# CAN.net
KiCad netlist of a schematic drawn in Altium Designer
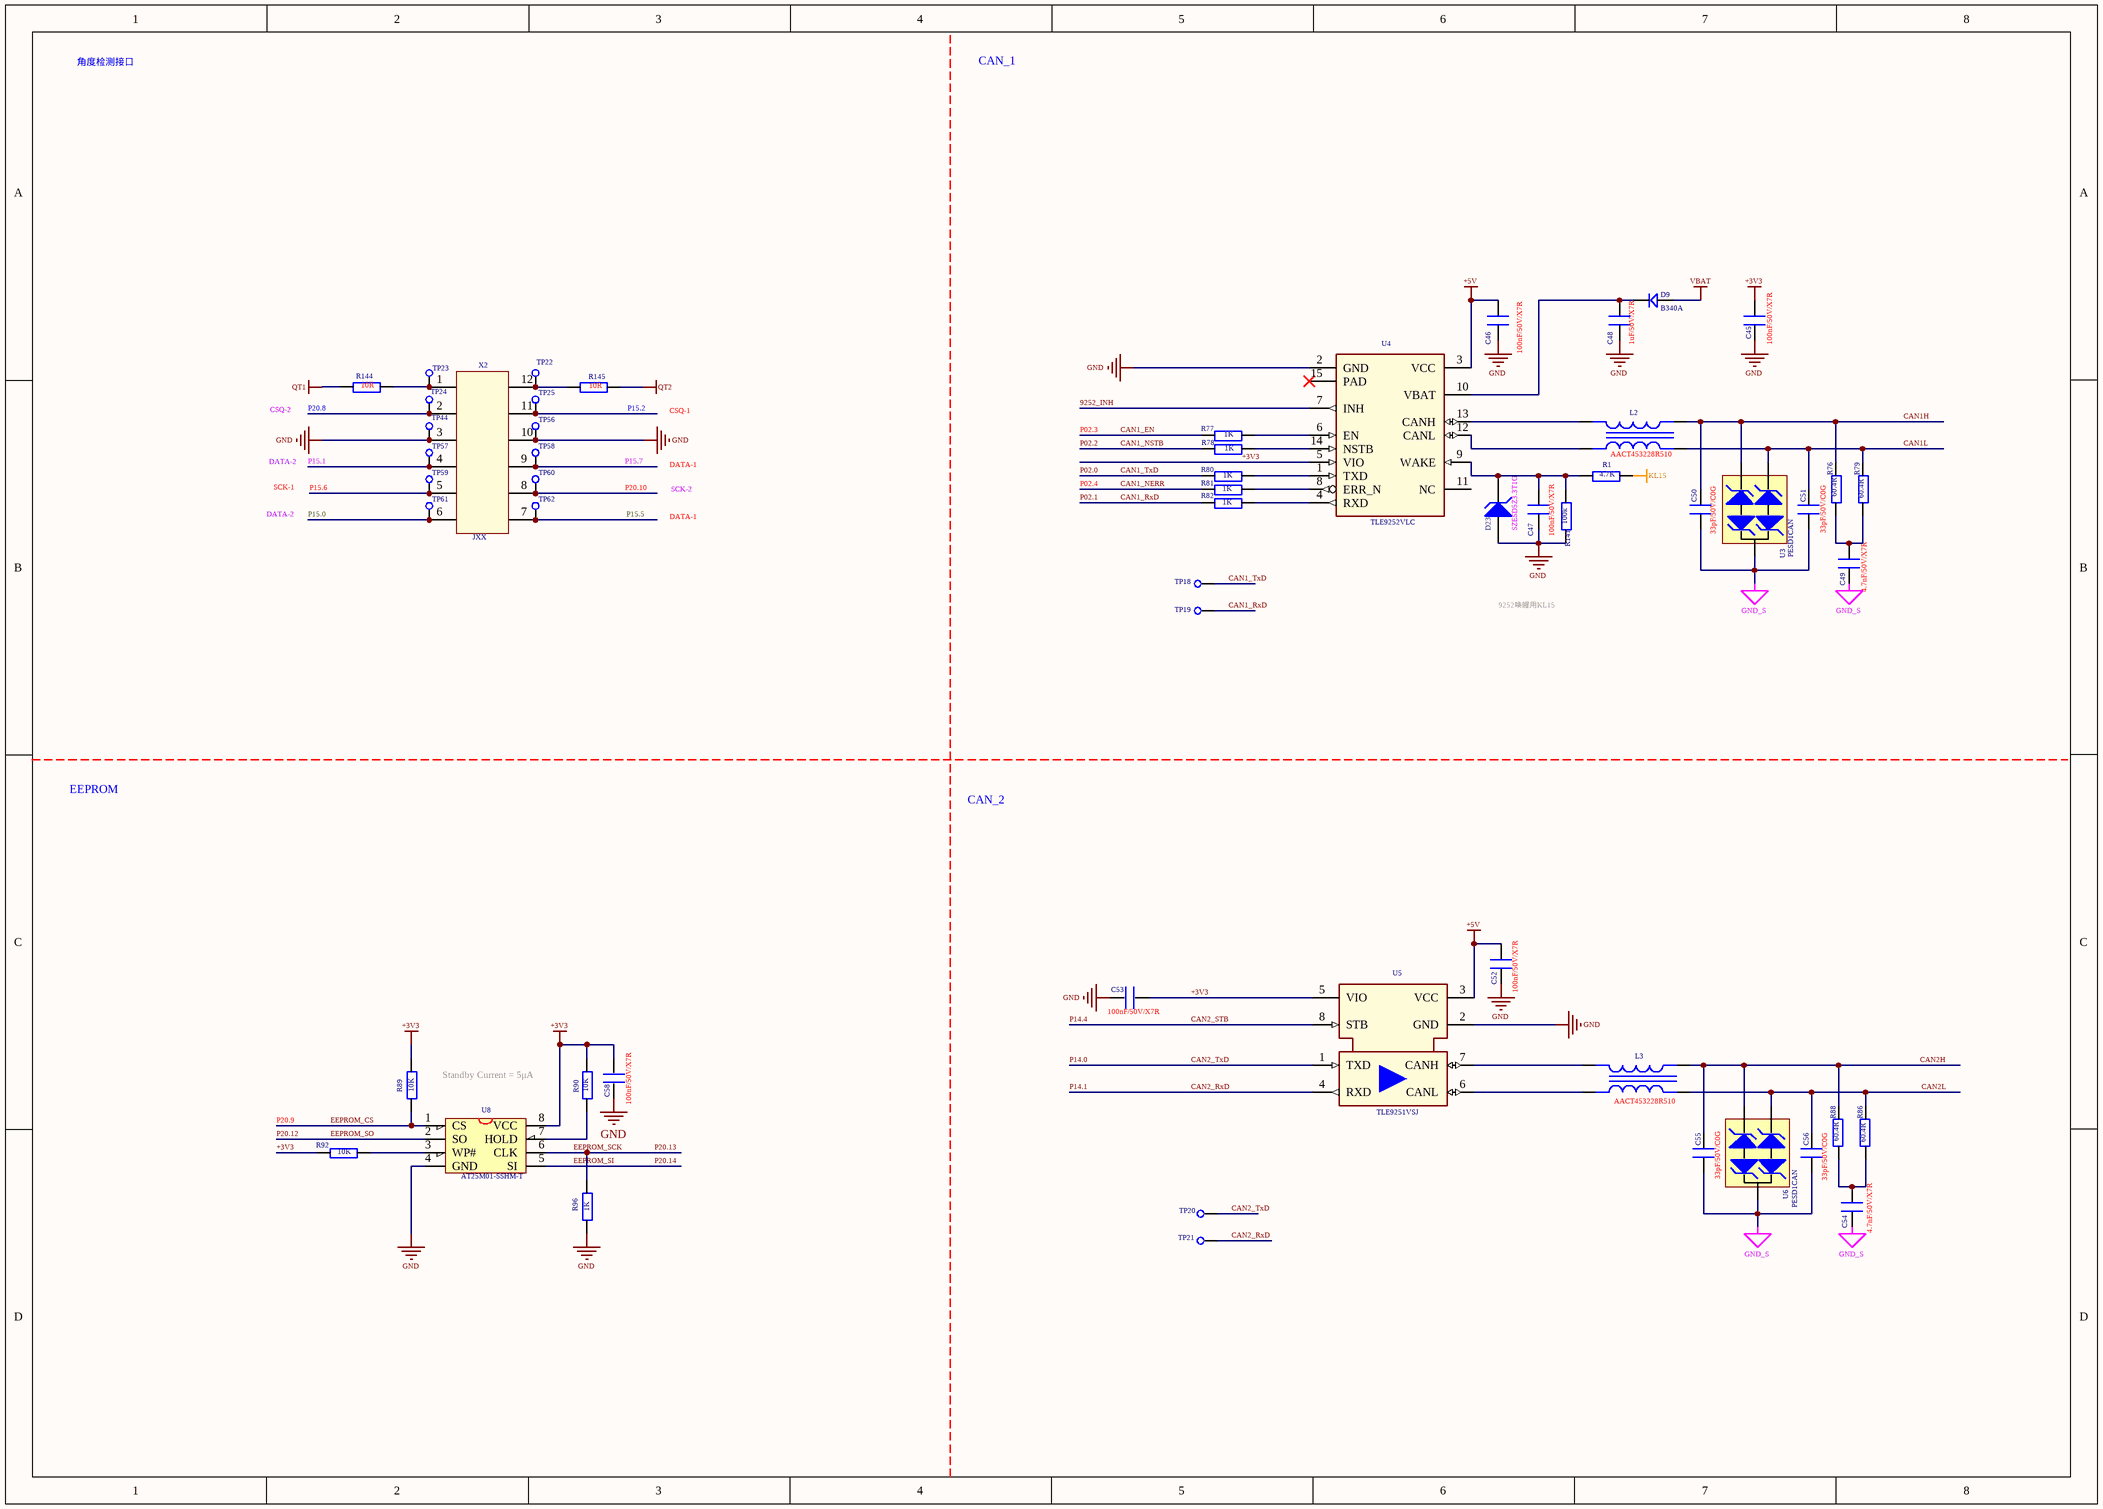
[diagram p0: CAN.SchDoc]

(export (version "E")
  (design (tool "Eeschema 10.0.6"))
  (components
    (comp (ref "C45")
      (value "100nF/50V/X7R")
      (footprint "C0603P")
      (libsource (lib "WarShip V3 STM32103封装库") (part "C"))
    )
    (comp (ref "C46")
      (value "100nF/50V/X7R")
      (footprint "C0603P")
      (libsource (lib "WarShip V3 STM32103封装库") (part "C"))
    )
    (comp (ref "C47")
      (value "100nF/50V/X7R")
      (footprint "C0603P")
      (libsource (lib "WarShip V3 STM32103封装库") (part "C"))
    )
    (comp (ref "C48")
      (value "1uF/50V/X7R")
      (footprint "C0805")
      (libsource (lib "WarShip V3 STM32103封装库") (part "C"))
    )
    (comp (ref "C49")
      (value "4.7nF/50V/X7R")
      (footprint "C0603P")
      (libsource (lib "WarShip V3 STM32103封装库") (part "C"))
    )
    (comp (ref "C50")
      (value "33pF/50V/C0G")
      (footprint "C0603P")
      (libsource (lib "WarShip V3 STM32103封装库") (part "C"))
    )
    (comp (ref "C51")
      (value "33pF/50V/C0G")
      (footprint "C0603P")
      (libsource (lib "WarShip V3 STM32103封装库") (part "C"))
    )
    (comp (ref "C52")
      (value "100nF/50V/X7R")
      (footprint "C0603P")
      (libsource (lib "WarShip V3 STM32103封装库") (part "C"))
    )
    (comp (ref "C53")
      (value "100nF/50V/X7R")
      (footprint "C0603P")
      (libsource (lib "WarShip V3 STM32103封装库") (part "C"))
    )
    (comp (ref "C54")
      (value "4.7nF/50V/X7R")
      (footprint "C0603P")
      (libsource (lib "WarShip V3 STM32103封装库") (part "C"))
    )
    (comp (ref "C55")
      (value "33pF/50V/C0G")
      (footprint "C0603P")
      (libsource (lib "WarShip V3 STM32103封装库") (part "C"))
    )
    (comp (ref "C56")
      (value "33pF/50V/C0G")
      (footprint "C0603P")
      (libsource (lib "WarShip V3 STM32103封装库") (part "C"))
    )
    (comp (ref "C58")
      (value "100nF/50V/X7R")
      (footprint "C0603P")
      (libsource (lib "WarShip V3 STM32103封装库") (part "C"))
    )
    (comp (ref "D9")
      (value "B340A")
      (footprint "DO-214AC")
      (libsource (lib "WarShip V3 STM32103封装库") (part "D"))
    )
    (comp (ref "D23")
      (value "SZESD5Z3.3T1G")
      (footprint "SOD-523F")
      (description "Zener Diode")
      (fields (field (name "PUBLISHER") "Altium Limited"))
      (libsource (lib "Miscellaneous Devices") (part "D Zener"))
    )
    (comp (ref "L2")
      (value "AACT453228R510")
      (footprint "ACT45B")
      (libsource (lib "zs_lib_wgs") (part "ACT45B-510-2P"))
    )
    (comp (ref "L3")
      (value "AACT453228R510")
      (footprint "ACT45B")
      (libsource (lib "zs_lib_wgs") (part "ACT45B-510-2P"))
    )
    (comp (ref "R1") (value "4.7K") (footprint "0603P") (libsource (lib "WarShip V3 STM32103封装库") (part "R")))
    (comp (ref "R76")
      (value "60.4R")
      (footprint "0603P")
      (libsource (lib "WarShip V3 STM32103封装库") (part "R"))
    )
    (comp (ref "R77") (value "1K") (footprint "0603P") (libsource (lib "WarShip V3 STM32103封装库") (part "R")))
    (comp (ref "R78") (value "1K") (footprint "0603P") (libsource (lib "WarShip V3 STM32103封装库") (part "R")))
    (comp (ref "R79")
      (value "60.4R")
      (footprint "0603P")
      (libsource (lib "WarShip V3 STM32103封装库") (part "R"))
    )
    (comp (ref "R80") (value "1K") (footprint "0603P") (libsource (lib "WarShip V3 STM32103封装库") (part "R")))
    (comp (ref "R81") (value "1K") (footprint "0603P") (libsource (lib "WarShip V3 STM32103封装库") (part "R")))
    (comp (ref "R82") (value "1K") (footprint "0603P") (libsource (lib "WarShip V3 STM32103封装库") (part "R")))
    (comp (ref "R86")
      (value "60.4R")
      (footprint "0603P")
      (libsource (lib "WarShip V3 STM32103封装库") (part "R"))
    )
    (comp (ref "R88")
      (value "60.4R")
      (footprint "0603P")
      (libsource (lib "WarShip V3 STM32103封装库") (part "R"))
    )
    (comp (ref "R89") (value "10K") (footprint "0603P") (libsource (lib "WarShip V3 STM32103封装库") (part "R")))
    (comp (ref "R90") (value "10K") (footprint "0603P") (libsource (lib "WarShip V3 STM32103封装库") (part "R")))
    (comp (ref "R92") (value "10K") (footprint "0603P") (libsource (lib "WarShip V3 STM32103封装库") (part "R")))
    (comp (ref "R96") (value "1K") (footprint "0603P") (libsource (lib "WarShip V3 STM32103封装库") (part "R")))
    (comp (ref "R141")
      (value "100k")
      (footprint "0603P")
      (libsource (lib "WarShip V3 STM32103封装库") (part "R"))
    )
    (comp (ref "R144")
      (value "10R")
      (footprint "0603P")
      (libsource (lib "WarShip V3 STM32103封装库") (part "R"))
    )
    (comp (ref "R145")
      (value "10R")
      (footprint "0603P")
      (libsource (lib "WarShip V3 STM32103封装库") (part "R"))
    )
    (comp (ref "TP18") (value "测试点") (footprint "测试点") (libsource (lib "") (part "测试点_1")))
    (comp (ref "TP19") (value "测试点") (footprint "测试点") (libsource (lib "") (part "测试点_1")))
    (comp (ref "TP20") (value "测试点") (footprint "测试点") (libsource (lib "") (part "测试点_1")))
    (comp (ref "TP21") (value "测试点") (footprint "测试点") (libsource (lib "") (part "测试点_1")))
    (comp (ref "TP22") (value "测试点") (footprint "测试点") (libsource (lib "yds") (part "测试点")))
    (comp (ref "TP23") (value "测试点") (footprint "测试点") (libsource (lib "yds") (part "测试点")))
    (comp (ref "TP24") (value "测试点") (footprint "测试点") (libsource (lib "yds") (part "测试点")))
    (comp (ref "TP25") (value "测试点") (footprint "测试点") (libsource (lib "yds") (part "测试点")))
    (comp (ref "TP44") (value "测试点") (footprint "测试点") (libsource (lib "yds") (part "测试点")))
    (comp (ref "TP56") (value "测试点") (footprint "测试点") (libsource (lib "yds") (part "测试点")))
    (comp (ref "TP57") (value "测试点") (footprint "测试点") (libsource (lib "yds") (part "测试点")))
    (comp (ref "TP58") (value "测试点") (footprint "测试点") (libsource (lib "yds") (part "测试点")))
    (comp (ref "TP59") (value "测试点") (footprint "测试点") (libsource (lib "yds") (part "测试点")))
    (comp (ref "TP60") (value "测试点") (footprint "测试点") (libsource (lib "yds") (part "测试点")))
    (comp (ref "TP61") (value "测试点") (footprint "测试点") (libsource (lib "yds") (part "测试点")))
    (comp (ref "TP62") (value "测试点") (footprint "测试点") (libsource (lib "yds") (part "测试点")))
    (comp (ref "U3")
      (value "PESD1CAN")
      (footprint "SOT-23R")
      (libsource (lib "zs_lib_wgs") (part "PESD1CAN"))
    )
    (comp (ref "U4")
      (value "TLE9252VLC")
      (footprint "SOP14")
      (description "High Speed CAN FD Transceiver")
      (fields (field (name "MANUFACTURER") "Infineon Technologies"))
      (libsource (lib "yds") (part "TLE9252VLC"))
    )
    (comp (ref "U5")
      (value "TLE9251VSJ")
      (footprint "SOIC127P600X175-8N-3")
      (description "High Speed CAN Transceiver")
      (fields (field (name "MANUFACTURER") "Infineon Technologies"))
      (libsource (lib "yds") (part "TLE9251VSJ"))
    )
    (comp (ref "U6")
      (value "PESD1CAN")
      (footprint "SOT-23R")
      (libsource (lib "zs_lib_wgs") (part "PESD1CAN"))
    )
    (comp (ref "U8")
      (value "AT25M01-SSHM-T")
      (footprint "SOIC-8")
      (description "W25X16;SST25VF016;MX25L1605")
      (libsource (lib "WarShip V3 STM32103封装库") (part "W25X16"))
    )
    (comp (ref "X2") (value "JXX") (footprint "HDR2X6") (libsource (lib "myTY_NEW") (part "JXX")))
  )
  (nets
    (net (code "1") (name "+3V3") (class "Default")
      (node (ref "C45") (pin "1") (pintype "passive"))
      (node (ref "C53") (pin "1") (pintype "passive"))
      (node (ref "C58") (pin "1") (pintype "passive"))
      (node (ref "R89") (pin "2") (pintype "passive"))
      (node (ref "R90") (pin "2") (pintype "passive"))
      (node (ref "R92") (pin "1") (pintype "passive"))
      (node (ref "U4") (pin "5") (pinfunction "VIO_5") (pintype "input"))
      (node (ref "U5") (pin "5") (pinfunction "VIO_5") (pintype "power_in"))
      (node (ref "U8") (pin "8") (pinfunction "VCC_8") (pintype "passive"))
    )
    (net (code "2") (name "+5V") (class "Default")
      (node (ref "C46") (pin "1") (pintype "passive"))
      (node (ref "C52") (pin "2") (pintype "passive"))
      (node (ref "U4") (pin "3") (pinfunction "VCC_3") (pintype "power_in"))
      (node (ref "U5") (pin "3") (pinfunction "VCC_3") (pintype "power_in"))
    )
    (net (code "3") (name "/9252_INH") (class "Default")
      (node (ref "U4") (pin "7") (pinfunction "INH_7") (pintype "output"))
    )
    (net (code "4") (name "/CAN1H") (class "Default")
      (node (ref "C50") (pin "2") (pintype "passive"))
      (node (ref "L2") (pin "3") (pinfunction "Sec-_3") (pintype "passive"))
      (node (ref "R76") (pin "2") (pintype "passive"))
      (node (ref "U3") (pin "2") (pinfunction "2_2") (pintype "passive"))
    )
    (net (code "5") (name "/CAN1L") (class "Default")
      (node (ref "C51") (pin "2") (pintype "passive"))
      (node (ref "L2") (pin "4") (pinfunction "Pri-_4") (pintype "passive"))
      (node (ref "R79") (pin "2") (pintype "passive"))
      (node (ref "U3") (pin "1") (pinfunction "1_1") (pintype "passive"))
    )
    (net (code "6") (name "/CAN1_EN") (class "Default") (node (ref "R77") (pin "1") (pintype "passive")))
    (net (code "7") (name "/CAN1_NERR") (class "Default") (node (ref "R81") (pin "1") (pintype "passive")))
    (net (code "8") (name "/CAN1_NSTB") (class "Default") (node (ref "R78") (pin "1") (pintype "passive")))
    (net (code "9") (name "/CAN1_RxD") (class "Default")
      (node (ref "R82") (pin "1") (pintype "passive"))
      (node (ref "TP19") (pin "1") (pinfunction "1_1") (pintype "passive"))
    )
    (net (code "10") (name "/CAN1_TxD") (class "Default")
      (node (ref "R80") (pin "1") (pintype "passive"))
      (node (ref "TP18") (pin "1") (pinfunction "1_1") (pintype "passive"))
    )
    (net (code "11") (name "/CAN2H") (class "Default")
      (node (ref "C55") (pin "2") (pintype "passive"))
      (node (ref "L3") (pin "3") (pinfunction "Sec-_3") (pintype "passive"))
      (node (ref "R88") (pin "1") (pintype "passive"))
      (node (ref "U6") (pin "2") (pinfunction "2_2") (pintype "passive"))
    )
    (net (code "12") (name "/CAN2L") (class "Default")
      (node (ref "C56") (pin "2") (pintype "passive"))
      (node (ref "L3") (pin "4") (pinfunction "Pri-_4") (pintype "passive"))
      (node (ref "R86") (pin "1") (pintype "passive"))
      (node (ref "U6") (pin "1") (pinfunction "1_1") (pintype "passive"))
    )
    (net (code "13") (name "/CAN2_RxD") (class "Default")
      (node (ref "TP21") (pin "1") (pinfunction "1_1") (pintype "passive"))
      (node (ref "U5") (pin "4") (pinfunction "RXD_4") (pintype "output"))
    )
    (net (code "14") (name "/CAN2_STB") (class "Default")
      (node (ref "U5") (pin "8") (pinfunction "STB_8") (pintype "input"))
    )
    (net (code "15") (name "/CAN2_TxD") (class "Default")
      (node (ref "TP20") (pin "1") (pinfunction "1_1") (pintype "passive"))
      (node (ref "U5") (pin "1") (pinfunction "TXD_1") (pintype "input"))
    )
    (net (code "20") (name "/EEPROM_CS") (class "Default")
      (node (ref "R89") (pin "1") (pintype "passive"))
      (node (ref "U8") (pin "1") (pinfunction "CS_1") (pintype "passive"))
    )
    (net (code "21") (name "/EEPROM_SCK") (class "Default")
      (node (ref "R96") (pin "2") (pintype "passive"))
      (node (ref "U8") (pin "6") (pinfunction "CLK_6") (pintype "passive"))
    )
    (net (code "22") (name "/EEPROM_SI") (class "Default")
      (node (ref "U8") (pin "5") (pinfunction "SI_5") (pintype "passive"))
    )
    (net (code "23") (name "/EEPROM_SO") (class "Default")
      (node (ref "U8") (pin "2") (pinfunction "SO_2") (pintype "passive"))
    )
    (net (code "24") (name "/P15.0") (class "Default")
      (node (ref "TP61") (pin "1") (pinfunction "1_1") (pintype "passive"))
      (node (ref "X2") (pin "6") (pinfunction "6_6") (pintype "passive"))
    )
    (net (code "25") (name "/P15.1") (class "Default")
      (node (ref "TP57") (pin "1") (pinfunction "1_1") (pintype "passive"))
      (node (ref "X2") (pin "4") (pinfunction "4_4") (pintype "passive"))
    )
    (net (code "26") (name "/P15.2") (class "Default")
      (node (ref "TP25") (pin "1") (pinfunction "1_1") (pintype "passive"))
      (node (ref "X2") (pin "11") (pinfunction "11_11") (pintype "passive"))
    )
    (net (code "27") (name "/P15.5") (class "Default")
      (node (ref "TP62") (pin "1") (pinfunction "1_1") (pintype "passive"))
      (node (ref "X2") (pin "7") (pinfunction "7_7") (pintype "passive"))
    )
    (net (code "28") (name "/P15.6") (class "Default")
      (node (ref "TP59") (pin "1") (pinfunction "1_1") (pintype "passive"))
      (node (ref "X2") (pin "5") (pinfunction "5_5") (pintype "passive"))
    )
    (net (code "29") (name "/P15.7") (class "Default")
      (node (ref "TP58") (pin "1") (pinfunction "1_1") (pintype "passive"))
      (node (ref "X2") (pin "9") (pinfunction "9_9") (pintype "passive"))
    )
    (net (code "30") (name "/P20.8") (class "Default")
      (node (ref "TP24") (pin "1") (pinfunction "1_1") (pintype "passive"))
      (node (ref "X2") (pin "2") (pinfunction "2_2") (pintype "passive"))
    )
    (net (code "31") (name "/P20.10") (class "Default")
      (node (ref "TP60") (pin "1") (pinfunction "1_1") (pintype "passive"))
      (node (ref "X2") (pin "8") (pinfunction "8_8") (pintype "passive"))
    )
    (net (code "34") (name "GND") (class "Default")
      (node (ref "C45") (pin "2") (pintype "passive"))
      (node (ref "C46") (pin "2") (pintype "passive"))
      (node (ref "C47") (pin "2") (pintype "passive"))
      (node (ref "C48") (pin "2") (pintype "passive"))
      (node (ref "C52") (pin "1") (pintype "passive"))
      (node (ref "C53") (pin "2") (pintype "passive"))
      (node (ref "C58") (pin "2") (pintype "passive"))
      (node (ref "D23") (pin "2") (pinfunction "A_2") (pintype "passive"))
      (node (ref "R141") (pin "1") (pintype "passive"))
      (node (ref "R96") (pin "1") (pintype "passive"))
      (node (ref "TP44") (pin "1") (pinfunction "1_1") (pintype "passive"))
      (node (ref "TP56") (pin "1") (pinfunction "1_1") (pintype "passive"))
      (node (ref "U4") (pin "2") (pinfunction "GND_2") (pintype "power_in"))
      (node (ref "U5") (pin "2") (pinfunction "GND_2") (pintype "power_in"))
      (node (ref "U8") (pin "4") (pinfunction "GND_4") (pintype "passive"))
      (node (ref "X2") (pin "10") (pinfunction "10_10") (pintype "passive"))
      (node (ref "X2") (pin "3") (pinfunction "3_3") (pintype "passive"))
    )
    (net (code "35") (name "GND_S") (class "Default")
      (node (ref "C49") (pin "1") (pintype "passive"))
      (node (ref "C50") (pin "1") (pintype "passive"))
      (node (ref "C51") (pin "1") (pintype "passive"))
      (node (ref "C54") (pin "1") (pintype "passive"))
      (node (ref "C55") (pin "1") (pintype "passive"))
      (node (ref "C56") (pin "1") (pintype "passive"))
      (node (ref "U3") (pin "3") (pinfunction "3_3") (pintype "passive"))
      (node (ref "U6") (pin "3") (pinfunction "3_3") (pintype "passive"))
    )
    (net (code "36") (name "KL15") (class "Default") (node (ref "R1") (pin "2") (pintype "passive")))
    (net (code "37") (name "Net-(C49-Pad2)") (class "Default")
      (node (ref "C49") (pin "2") (pintype "passive"))
      (node (ref "R76") (pin "1") (pintype "passive"))
      (node (ref "R79") (pin "1") (pintype "passive"))
    )
    (net (code "38") (name "Net-(C54-Pad2)") (class "Default")
      (node (ref "C54") (pin "2") (pintype "passive"))
      (node (ref "R86") (pin "2") (pintype "passive"))
      (node (ref "R88") (pin "2") (pintype "passive"))
    )
    (net (code "39") (name "Net-(D23-K)") (class "Default")
      (node (ref "C47") (pin "1") (pintype "passive"))
      (node (ref "D23") (pin "1") (pinfunction "K_1") (pintype "passive"))
      (node (ref "R1") (pin "1") (pintype "passive"))
      (node (ref "R141") (pin "2") (pintype "passive"))
      (node (ref "U4") (pin "9") (pinfunction "WAKE_9") (pintype "input"))
    )
    (net (code "40") (name "Net-(L2-Pri+)") (class "Default")
      (node (ref "L2") (pin "1") (pinfunction "Pri+_1") (pintype "passive"))
      (node (ref "U4") (pin "12") (pinfunction "CANL_12") (pintype "bidirectional"))
    )
    (net (code "41") (name "Net-(L2-Sec+)") (class "Default")
      (node (ref "L2") (pin "2") (pinfunction "Sec+_2") (pintype "passive"))
      (node (ref "U4") (pin "13") (pinfunction "CANH_13") (pintype "bidirectional"))
    )
    (net (code "42") (name "Net-(L3-Pri+)") (class "Default")
      (node (ref "L3") (pin "1") (pinfunction "Pri+_1") (pintype "passive"))
      (node (ref "U5") (pin "6") (pinfunction "CANL_6") (pintype "bidirectional"))
    )
    (net (code "43") (name "Net-(L3-Sec+)") (class "Default")
      (node (ref "L3") (pin "2") (pinfunction "Sec+_2") (pintype "passive"))
      (node (ref "U5") (pin "7") (pinfunction "CANH_7") (pintype "bidirectional"))
    )
    (net (code "44") (name "Net-(R144-Pad2)") (class "Default")
      (node (ref "R144") (pin "2") (pintype "passive"))
      (node (ref "TP23") (pin "1") (pinfunction "1_1") (pintype "passive"))
      (node (ref "X2") (pin "1") (pinfunction "1_1") (pintype "passive"))
    )
    (net (code "45") (name "Net-(R145-Pad1)") (class "Default")
      (node (ref "R145") (pin "1") (pintype "passive"))
      (node (ref "TP22") (pin "1") (pinfunction "1_1") (pintype "passive"))
      (node (ref "X2") (pin "12") (pinfunction "12_12") (pintype "passive"))
    )
    (net (code "46") (name "Net-(U4-EN)") (class "Default")
      (node (ref "R77") (pin "2") (pintype "passive"))
      (node (ref "U4") (pin "6") (pinfunction "EN_6") (pintype "input"))
    )
    (net (code "47") (name "Net-(U4-ERR_N)") (class "Default")
      (node (ref "R81") (pin "2") (pintype "passive"))
      (node (ref "U4") (pin "8") (pinfunction "ERR_N_8") (pintype "output"))
    )
    (net (code "48") (name "Net-(U4-NSTB)") (class "Default")
      (node (ref "R78") (pin "2") (pintype "passive"))
      (node (ref "U4") (pin "14") (pinfunction "NSTB_14") (pintype "input"))
    )
    (net (code "49") (name "Net-(U4-RXD)") (class "Default")
      (node (ref "R82") (pin "2") (pintype "passive"))
      (node (ref "U4") (pin "4") (pinfunction "RXD_4") (pintype "output"))
    )
    (net (code "50") (name "Net-(U4-TXD)") (class "Default")
      (node (ref "R80") (pin "2") (pintype "passive"))
      (node (ref "U4") (pin "1") (pinfunction "TXD_1") (pintype "input"))
    )
    (net (code "51") (name "Net-(U4-VBAT)") (class "Default")
      (node (ref "C48") (pin "1") (pintype "passive"))
      (node (ref "D9") (pin "2") (pintype "passive"))
      (node (ref "U4") (pin "10") (pinfunction "VBAT_10") (pintype "power_in"))
    )
    (net (code "52") (name "Net-(U8-HOLD)") (class "Default")
      (node (ref "R90") (pin "1") (pintype "passive"))
      (node (ref "U8") (pin "7") (pinfunction "HOLD_7") (pintype "passive"))
    )
    (net (code "53") (name "Net-(U8-WP#)") (class "Default")
      (node (ref "R92") (pin "2") (pintype "passive"))
      (node (ref "U8") (pin "3") (pinfunction "WP#_3") (pintype "passive"))
    )
    (net (code "54") (name "QT1") (class "Default") (node (ref "R144") (pin "1") (pintype "passive")))
    (net (code "55") (name "QT2") (class "Default") (node (ref "R145") (pin "2") (pintype "passive")))
    (net (code "56") (name "VBAT") (class "Default") (node (ref "D9") (pin "1") (pintype "passive")))
    (net (code "57") (name "unconnected-(U4-NC-Pad11)") (class "Default")
      (node (ref "U4") (pin "11") (pinfunction "NC_11") (pintype "passive"))
    )
    (net (code "58") (name "unconnected-(U4-PAD-Pad15)") (class "Default")
      (node (ref "U4") (pin "15") (pinfunction "PAD_15") (pintype "power_in+no_connect"))
    )
  )
)
